# L_H_ext_rgb.net
KiCad netlist of a schematic drawn in EAGLE
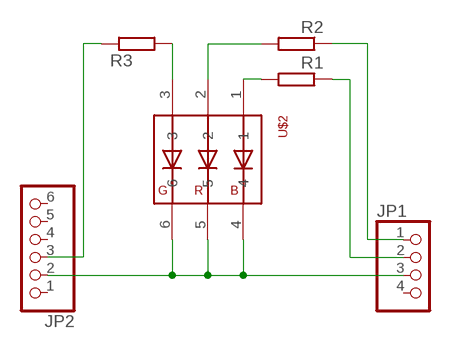
[diagram p0: schematic, sheet 1]

(export (version "E")
  (design (tool "Eeschema 10.0.6"))
  (components
    (comp (ref "JP1")
      (value "PINHD-1X4")
      (footprint "eagle-import:1X04")
      (libsource (lib "eagle-import") (part "PINHD-1X4"))
    )
    (comp (ref "JP2")
      (value "PINHD-1X6")
      (footprint "eagle-import:1X06")
      (libsource (lib "eagle-import") (part "PINHD-1X6"))
    )
    (comp (ref "R1")
      (value "R-EU_R0603")
      (footprint "eagle-import:R0603")
      (libsource (lib "eagle-import") (part "R-EU_R0603"))
    )
    (comp (ref "R2")
      (value "R-EU_R0603")
      (footprint "eagle-import:R0603")
      (libsource (lib "eagle-import") (part "R-EU_R0603"))
    )
    (comp (ref "R3")
      (value "R-EU_R0603")
      (footprint "eagle-import:R0603")
      (libsource (lib "eagle-import") (part "R-EU_R0603"))
    )
    (comp (ref "U$2")
      (value "RGB_WW-FCE50TC-Q1")
      (footprint "eagle-import:RGB_WW-FCE50TC-Q1")
      (libsource (lib "eagle-import") (part "RGB_WW-FCE50TC-Q1"))
    )
  )
  (nets
    (net (code "1") (name "Net-(JP1-Pad1)") (class "Default")
      (node (ref "JP1") (pin "1") (pinfunction "1_1") (pintype "passive"))
      (node (ref "R2") (pin "1") (pinfunction "1_1") (pintype "passive"))
    )
    (net (code "2") (name "Net-(JP1-Pad2)") (class "Default")
      (node (ref "JP1") (pin "2") (pinfunction "2_2") (pintype "passive"))
      (node (ref "R1") (pin "1") (pinfunction "1_1") (pintype "passive"))
    )
    (net (code "3") (name "Net-(JP1-Pad3)") (class "Default")
      (node (ref "JP1") (pin "3") (pinfunction "3_3") (pintype "passive"))
      (node (ref "JP2") (pin "2") (pinfunction "2_2") (pintype "passive"))
      (node (ref "U$2") (pin "4") (pinfunction "4_4") (pintype "bidirectional"))
      (node (ref "U$2") (pin "5") (pinfunction "5_5") (pintype "bidirectional"))
      (node (ref "U$2") (pin "6") (pinfunction "6_6") (pintype "bidirectional"))
    )
    (net (code "4") (name "Net-(JP2-Pad3)") (class "Default")
      (node (ref "JP2") (pin "3") (pinfunction "3_3") (pintype "passive"))
      (node (ref "R3") (pin "1") (pinfunction "1_1") (pintype "passive"))
    )
    (net (code "5") (name "Net-(R1-Pad2)") (class "Default")
      (node (ref "R1") (pin "2") (pinfunction "2_2") (pintype "passive"))
      (node (ref "U$2") (pin "1") (pinfunction "1_1") (pintype "bidirectional"))
    )
    (net (code "6") (name "Net-(R2-Pad2)") (class "Default")
      (node (ref "R2") (pin "2") (pinfunction "2_2") (pintype "passive"))
      (node (ref "U$2") (pin "2") (pinfunction "2_2") (pintype "bidirectional"))
    )
    (net (code "7") (name "Net-(R3-Pad2)") (class "Default")
      (node (ref "R3") (pin "2") (pinfunction "2_2") (pintype "passive"))
      (node (ref "U$2") (pin "3") (pinfunction "3_3") (pintype "bidirectional"))
    )
    (net (code "8") (name "unconnected-(JP1-Pad4)") (class "Default")
      (node (ref "JP1") (pin "4") (pinfunction "4_4") (pintype "passive"))
    )
    (net (code "9") (name "unconnected-(JP2-Pad1)") (class "Default")
      (node (ref "JP2") (pin "1") (pinfunction "1_1") (pintype "passive"))
    )
    (net (code "10") (name "unconnected-(JP2-Pad4)") (class "Default")
      (node (ref "JP2") (pin "4") (pinfunction "4_4") (pintype "passive"))
    )
    (net (code "11") (name "unconnected-(JP2-Pad5)") (class "Default")
      (node (ref "JP2") (pin "5") (pinfunction "5_5") (pintype "passive"))
    )
    (net (code "12") (name "unconnected-(JP2-Pad6)") (class "Default")
      (node (ref "JP2") (pin "6") (pinfunction "6_6") (pintype "passive"))
    )
  )
)
